# V0p2_Main_PCB2.net
KiCad netlist of a schematic drawn in EAGLE
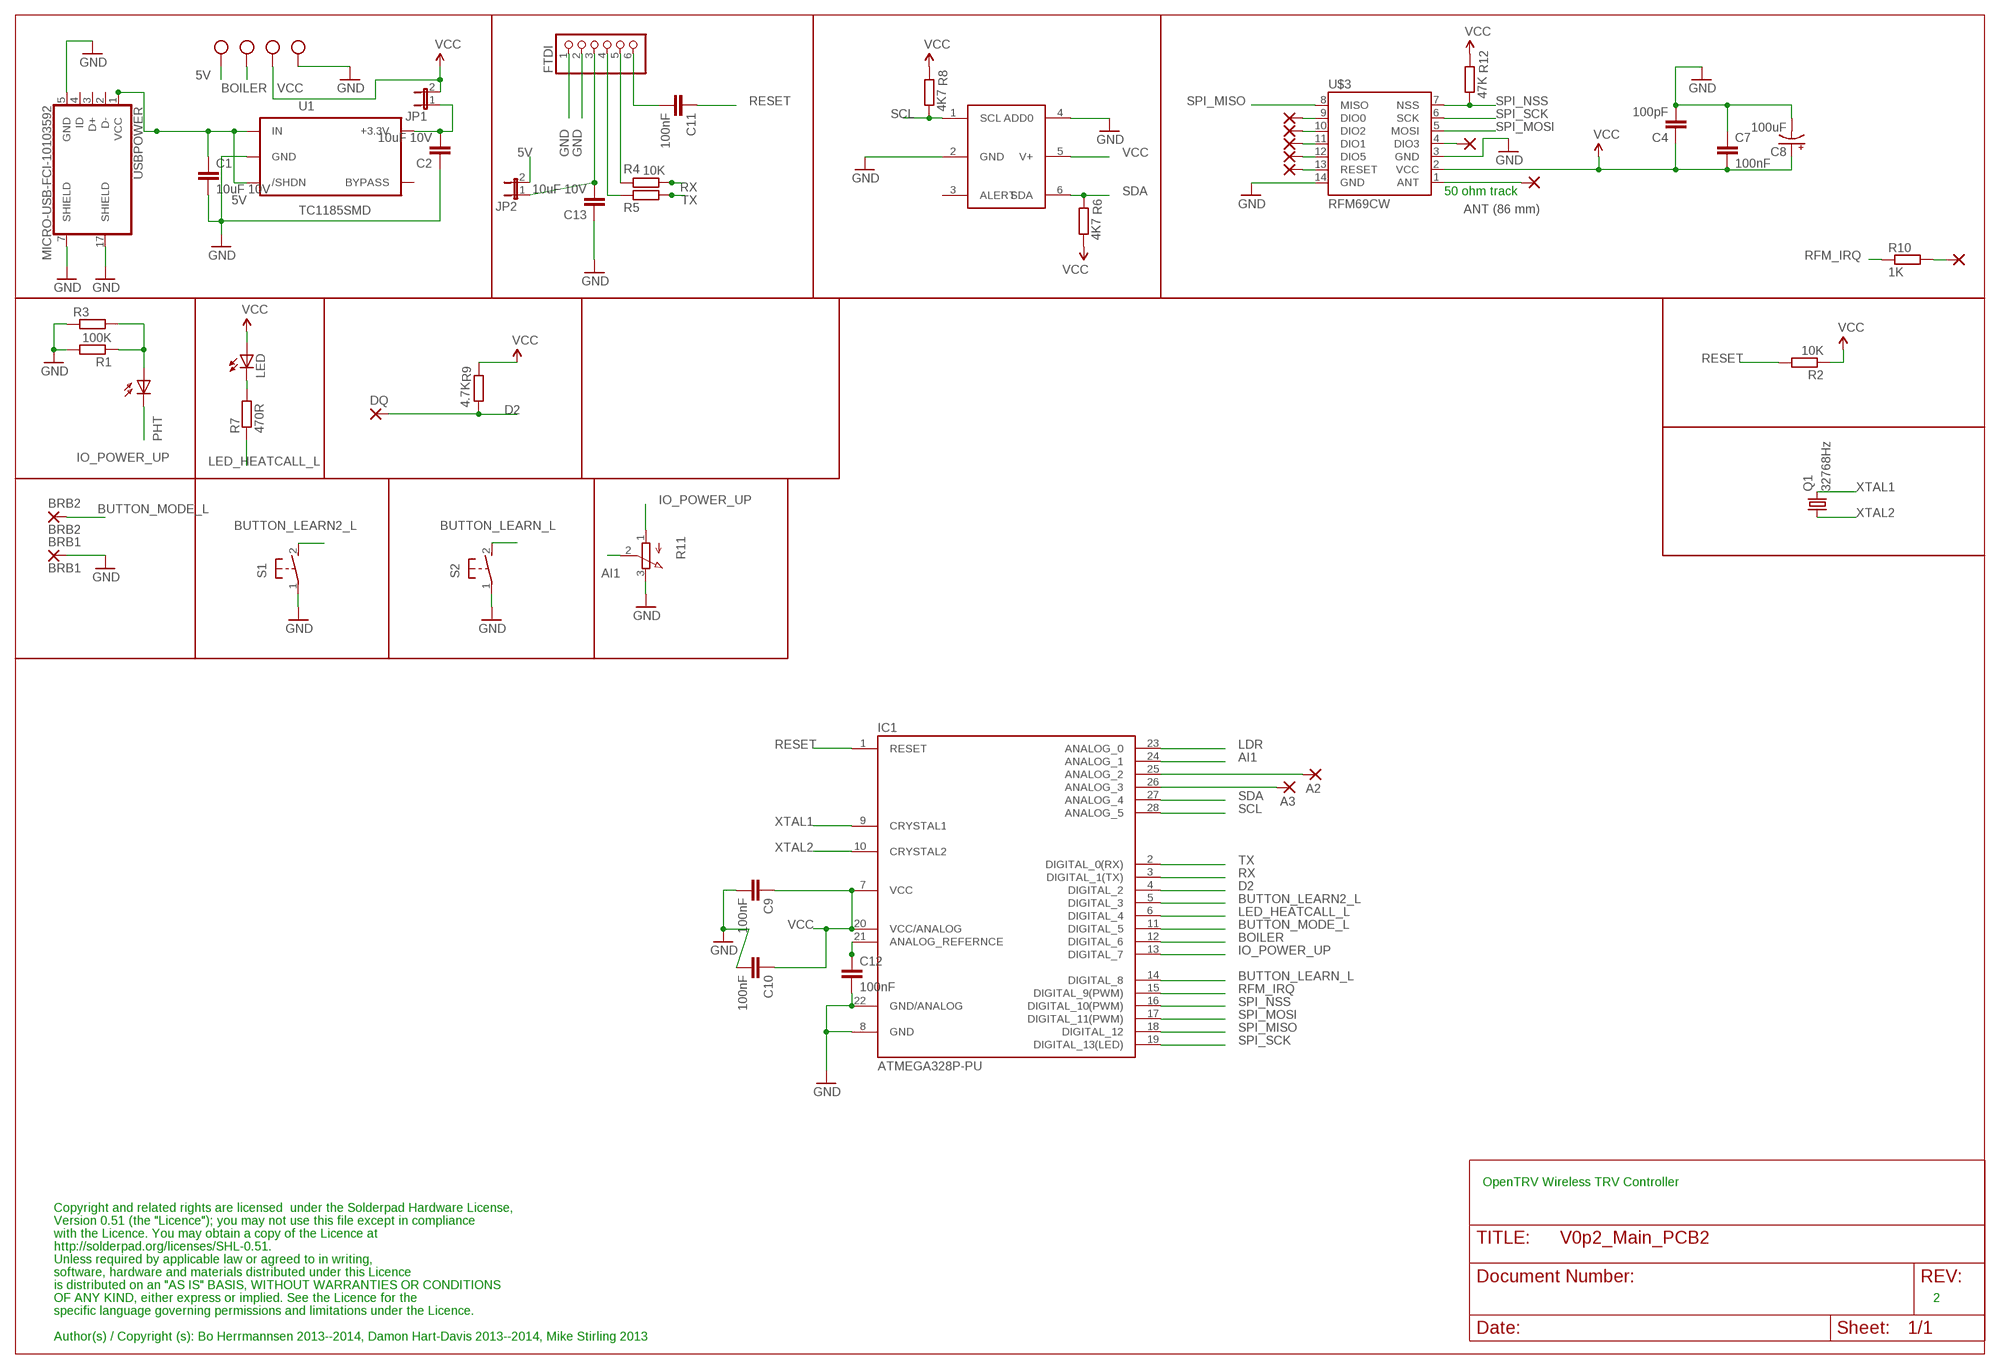
[diagram p0: schematic, sheet 1]

(export (version "E")
  (design (tool "Eeschema 10.0.6"))
  (components
    (comp (ref "A2")
      (value "2,15/1,0")
      (footprint "eagle-import:2,15_1,0")
      (libsource (lib "eagle-import") (part "2,15/1,0"))
    )
    (comp (ref "A3")
      (value "2,15/1,0")
      (footprint "eagle-import:2,15_1,0")
      (libsource (lib "eagle-import") (part "2,15/1,0"))
    )
    (comp (ref "ANT")
      (value "ANT (86 mm)")
      (footprint "eagle-import:2,15_1,0")
      (libsource (lib "eagle-import") (part "2,15/1,0"))
    )
    (comp (ref "BRB1")
      (value "BRB1")
      (footprint "eagle-import:2,15_1,0")
      (libsource (lib "eagle-import") (part "2,15/1,0"))
    )
    (comp (ref "BRB2")
      (value "BRB2")
      (footprint "eagle-import:2,15_1,0")
      (libsource (lib "eagle-import") (part "2,15/1,0"))
    )
    (comp (ref "C1")
      (value "10uF 10V")
      (footprint "eagle-import:C0603")
      (libsource (lib "eagle-import") (part "C-EUC0603"))
    )
    (comp (ref "C2")
      (value "10uF 10V")
      (footprint "eagle-import:C0603")
      (libsource (lib "eagle-import") (part "C-EUC0603"))
    )
    (comp (ref "C4")
      (value "100pF")
      (footprint "eagle-import:C0603")
      (libsource (lib "eagle-import") (part "C-EUC0603"))
    )
    (comp (ref "C7")
      (value "100nF")
      (footprint "eagle-import:C0603")
      (libsource (lib "eagle-import") (part "C-EUC0603"))
    )
    (comp (ref "C8")
      (value "100uF")
      (footprint "eagle-import:EIA3216")
      (libsource (lib "eagle-import") (part "CAP_POL1206"))
    )
    (comp (ref "C9")
      (value "100nF")
      (footprint "eagle-import:C0603")
      (libsource (lib "eagle-import") (part "C-EUC0603"))
    )
    (comp (ref "C10")
      (value "100nF")
      (footprint "eagle-import:C0603")
      (libsource (lib "eagle-import") (part "C-EUC0603"))
    )
    (comp (ref "C11")
      (value "100nF")
      (footprint "eagle-import:C0603")
      (libsource (lib "eagle-import") (part "C-EUC0603"))
    )
    (comp (ref "C12")
      (value "100nF")
      (footprint "eagle-import:C0603")
      (libsource (lib "eagle-import") (part "C-EUC0603"))
    )
    (comp (ref "C13")
      (value "10uF 10V")
      (footprint "eagle-import:C0603")
      (libsource (lib "eagle-import") (part "C-EUC0603"))
    )
    (comp (ref "DIO0")
      (value "ANT (86 mm)")
      (footprint "eagle-import:2,15_1,0")
      (libsource (lib "eagle-import") (part "2,15/1,0"))
    )
    (comp (ref "DIO1")
      (value "ANT (86 mm)")
      (footprint "eagle-import:2,15_1,0")
      (libsource (lib "eagle-import") (part "2,15/1,0"))
    )
    (comp (ref "DIO2")
      (value "ANT (86 mm)")
      (footprint "eagle-import:2,15_1,0")
      (libsource (lib "eagle-import") (part "2,15/1,0"))
    )
    (comp (ref "DIO3")
      (value "ANT (86 mm)")
      (footprint "eagle-import:2,15_1,0")
      (libsource (lib "eagle-import") (part "2,15/1,0"))
    )
    (comp (ref "DIO5")
      (value "ANT (86 mm)")
      (footprint "eagle-import:2,15_1,0")
      (libsource (lib "eagle-import") (part "2,15/1,0"))
    )
    (comp (ref "DQ")
      (value "2,15/1,0")
      (footprint "eagle-import:2,15_1,0")
      (libsource (lib "eagle-import") (part "2,15/1,0"))
    )
    (comp (ref "FTDI")
      (value "PINHD-1X6/90")
      (footprint "eagle-import:1X06_90")
      (libsource (lib "eagle-import") (part "PINHD-1X6/90"))
    )
    (comp (ref "IC1")
      (value "ATMEGA328P-PU")
      (footprint "eagle-import:DIL28-3")
      (libsource (lib "eagle-import") (part "ATMEGA8-PU"))
    )
    (comp (ref "IRQ")
      (value "ANT (86 mm)")
      (footprint "eagle-import:2,15_1,0")
      (libsource (lib "eagle-import") (part "2,15/1,0"))
    )
    (comp (ref "JP1")
      (value "JP1E")
      (footprint "eagle-import:JP1")
      (libsource (lib "eagle-import") (part "JP1E"))
    )
    (comp (ref "JP2")
      (value "JP1E")
      (footprint "eagle-import:JP1")
      (libsource (lib "eagle-import") (part "JP1E"))
    )
    (comp (ref "LED")
      (value "LED3MM")
      (footprint "eagle-import:LED3MM")
      (libsource (lib "eagle-import") (part "LED3MM"))
    )
    (comp (ref "PHT")
      (value "BPX65")
      (footprint "eagle-import:BPX65")
      (fields (field (name "MPN") "BPX65."))
      (libsource (lib "eagle-import") (part "BPX65"))
    )
    (comp (ref "Q1")
      (value "32768Hz")
      (footprint "eagle-import:MC-306")
      (fields (field (name "MPN") "MC-306 60.0KHZ  100PPM ,12.5PF"))
      (libsource (lib "eagle-import") (part "MC-306"))
    )
    (comp (ref "R1")
      (value "100K")
      (footprint "eagle-import:R0603")
      (libsource (lib "eagle-import") (part "R-EU_R0603"))
    )
    (comp (ref "R2")
      (value "10K")
      (footprint "eagle-import:R0603")
      (libsource (lib "eagle-import") (part "R-EU_R0603"))
    )
    (comp (ref "R3")
      (value "R-EU_0309/V")
      (footprint "eagle-import:0309V")
      (libsource (lib "eagle-import") (part "R-EU_0309/V"))
    )
    (comp (ref "R4")
      (value "10K")
      (footprint "eagle-import:R0603")
      (libsource (lib "eagle-import") (part "R-EU_R0603"))
    )
    (comp (ref "R5")
      (value "10K")
      (footprint "eagle-import:R0603")
      (libsource (lib "eagle-import") (part "R-EU_R0603"))
    )
    (comp (ref "R6")
      (value "4K7")
      (footprint "eagle-import:R0603")
      (libsource (lib "eagle-import") (part "R-EU_R0603"))
    )
    (comp (ref "R7")
      (value "470R")
      (footprint "eagle-import:R0603")
      (libsource (lib "eagle-import") (part "R-EU_R0603"))
    )
    (comp (ref "R8")
      (value "4K7")
      (footprint "eagle-import:R0603")
      (libsource (lib "eagle-import") (part "R-EU_R0603"))
    )
    (comp (ref "R9")
      (value "4.7K")
      (footprint "eagle-import:R0603")
      (libsource (lib "eagle-import") (part "R-EU_R0603"))
    )
    (comp (ref "R10")
      (value "1K")
      (footprint "eagle-import:R0603")
      (libsource (lib "eagle-import") (part "R-EU_R0603"))
    )
    (comp (ref "R11")
      (value "EVUE2A")
      (footprint "eagle-import:EVUE")
      (libsource (lib "eagle-import") (part "EVUE2A"))
    )
    (comp (ref "R12")
      (value "47K")
      (footprint "eagle-import:R0603")
      (libsource (lib "eagle-import") (part "R-EU_R0603"))
    )
    (comp (ref "RST")
      (value "ANT (86 mm)")
      (footprint "eagle-import:2,15_1,0")
      (libsource (lib "eagle-import") (part "2,15/1,0"))
    )
    (comp (ref "S1")
      (value "31-XX")
      (footprint "eagle-import:B3F-31XX")
      (libsource (lib "eagle-import") (part "31-XX"))
    )
    (comp (ref "S2")
      (value "31-XX")
      (footprint "eagle-import:B3F-31XX")
      (libsource (lib "eagle-import") (part "31-XX"))
    )
    (comp (ref "TMP1")
      (value "TMP1")
      (footprint "eagle-import:TMP112")
      (libsource (lib "eagle-import") (part "TMP112"))
    )
    (comp (ref "U$3")
      (value "RFM69CW")
      (footprint "eagle-import:RFM69")
      (libsource (lib "eagle-import") (part "RFM69SMD"))
    )
    (comp (ref "U1")
      (value "TC1185SMD")
      (footprint "eagle-import:TC1185")
      (libsource (lib "eagle-import") (part "TC1185SMD"))
    )
    (comp (ref "USBPOWER")
      (value "MICRO-USB-FCI-10103592")
      (footprint "eagle-import:MICRO-USB-FCI-10103592")
      (libsource (lib "eagle-import") (part "MICRO-USB-FCI-10103592"))
    )
    (comp (ref "X1")
      (value "W237-102")
      (footprint "eagle-import:SCREWTERMINAL")
      (fields (field (name "MPN") "237-102"))
      (libsource (lib "eagle-import") (part "W237-102"))
    )
    (comp (ref "X2")
      (value "W237-102")
      (footprint "eagle-import:SCREWTERMINAL")
      (fields (field (name "MPN") "237-102"))
      (libsource (lib "eagle-import") (part "W237-102"))
    )
  )
  (nets
    (net (code "1") (name "/5V") (class "Default")
      (node (ref "C1") (pin "1") (pinfunction "1_1") (pintype "passive"))
      (node (ref "JP2") (pin "2") (pinfunction "2_2") (pintype "passive"))
      (node (ref "U1") (pin "1") (pinfunction "IN_1") (pintype "passive"))
      (node (ref "U1") (pin "3") (pinfunction "/SHDN_3") (pintype "passive"))
      (node (ref "USBPOWER") (pin "1") (pinfunction "VCC_1") (pintype "bidirectional"))
      (node (ref "X1") (pin "2") (pinfunction "KL_2") (pintype "passive"))
    )
    (net (code "2") (name "/AI1") (class "Default")
      (node (ref "IC1") (pin "24") (pinfunction "ANALOG_1_24") (pintype "bidirectional"))
      (node (ref "R11") (pin "2") (pinfunction "S_2") (pintype "passive"))
    )
    (net (code "3") (name "/BOILER") (class "Default")
      (node (ref "IC1") (pin "12") (pinfunction "DIGITAL_6_12") (pintype "bidirectional"))
      (node (ref "X1") (pin "1") (pinfunction "KL_1") (pintype "passive"))
    )
    (net (code "4") (name "/BUTTON_LEARN2_L") (class "Default")
      (node (ref "IC1") (pin "5") (pinfunction "DIGITAL_3_5") (pintype "bidirectional"))
      (node (ref "S1") (pin "2") (pinfunction "S_2") (pintype "passive"))
    )
    (net (code "5") (name "/BUTTON_LEARN_L") (class "Default")
      (node (ref "IC1") (pin "14") (pinfunction "DIGITAL_8_14") (pintype "bidirectional"))
      (node (ref "S2") (pin "2") (pinfunction "S_2") (pintype "passive"))
    )
    (net (code "6") (name "/BUTTON_MODE_L") (class "Default")
      (node (ref "BRB2") (pin "1") (pinfunction "P_1") (pintype "passive"))
      (node (ref "IC1") (pin "11") (pinfunction "DIGITAL_5_11") (pintype "bidirectional"))
    )
    (net (code "7") (name "/D2") (class "Default")
      (node (ref "DQ") (pin "1") (pinfunction "P_1") (pintype "passive"))
      (node (ref "IC1") (pin "4") (pinfunction "DIGITAL_2_4") (pintype "bidirectional"))
      (node (ref "R9") (pin "1") (pinfunction "1_1") (pintype "passive"))
    )
    (net (code "8") (name "/IO_POWER_UP") (class "Default")
      (node (ref "IC1") (pin "13") (pinfunction "DIGITAL_7_13") (pintype "bidirectional"))
      (node (ref "PHT") (pin "K") (pinfunction "C_K") (pintype "passive"))
      (node (ref "R11") (pin "1") (pinfunction "A_1") (pintype "passive"))
    )
    (net (code "9") (name "/LDR") (class "Default")
      (node (ref "IC1") (pin "23") (pinfunction "ANALOG_0_23") (pintype "bidirectional"))
      (node (ref "PHT") (pin "A") (pinfunction "A_A") (pintype "passive"))
      (node (ref "R1") (pin "1") (pinfunction "1_1") (pintype "passive"))
      (node (ref "R3") (pin "2") (pinfunction "2_2") (pintype "passive"))
    )
    (net (code "10") (name "/LED_HEATCALL_L") (class "Default")
      (node (ref "IC1") (pin "6") (pinfunction "DIGITAL_4_6") (pintype "bidirectional"))
      (node (ref "R7") (pin "1") (pinfunction "1_1") (pintype "passive"))
    )
    (net (code "11") (name "/RESET") (class "Default")
      (node (ref "C11") (pin "1") (pinfunction "1_1") (pintype "passive"))
      (node (ref "IC1") (pin "1") (pinfunction "RESET_1") (pintype "bidirectional"))
      (node (ref "R2") (pin "2") (pinfunction "2_2") (pintype "passive"))
    )
    (net (code "12") (name "/RFM_IRQ") (class "Default")
      (node (ref "IC1") (pin "15") (pinfunction "DIGITAL_9(PWM)_15") (pintype "bidirectional"))
      (node (ref "R10") (pin "1") (pinfunction "1_1") (pintype "passive"))
    )
    (net (code "13") (name "/RX") (class "Default")
      (node (ref "IC1") (pin "3") (pinfunction "DIGITAL_1(TX)_3") (pintype "bidirectional"))
      (node (ref "R4") (pin "1") (pinfunction "1_1") (pintype "passive"))
    )
    (net (code "14") (name "/SCL") (class "Default")
      (node (ref "IC1") (pin "28") (pinfunction "ANALOG_5_28") (pintype "bidirectional"))
      (node (ref "R8") (pin "1") (pinfunction "1_1") (pintype "passive"))
      (node (ref "TMP1") (pin "1") (pinfunction "SCL_1") (pintype "bidirectional"))
    )
    (net (code "15") (name "/SDA") (class "Default")
      (node (ref "IC1") (pin "27") (pinfunction "ANALOG_4_27") (pintype "bidirectional"))
      (node (ref "R6") (pin "2") (pinfunction "2_2") (pintype "passive"))
      (node (ref "TMP1") (pin "6") (pinfunction "SDA_6") (pintype "bidirectional"))
    )
    (net (code "16") (name "/SPI_MISO") (class "Default")
      (node (ref "IC1") (pin "18") (pinfunction "DIGITAL_12_18") (pintype "bidirectional"))
      (node (ref "U$3") (pin "8") (pinfunction "MISO_8") (pintype "input"))
    )
    (net (code "17") (name "/SPI_MOSI") (class "Default")
      (node (ref "IC1") (pin "17") (pinfunction "DIGITAL_11(PWM)_17") (pintype "bidirectional"))
      (node (ref "U$3") (pin "5") (pinfunction "MOSI_5") (pintype "input"))
    )
    (net (code "18") (name "/SPI_NSS") (class "Default")
      (node (ref "IC1") (pin "16") (pinfunction "DIGITAL_10(PWM)_16") (pintype "bidirectional"))
      (node (ref "R12") (pin "1") (pinfunction "1_1") (pintype "passive"))
      (node (ref "U$3") (pin "7") (pinfunction "NSS_7") (pintype "output"))
    )
    (net (code "19") (name "/SPI_SCK") (class "Default")
      (node (ref "IC1") (pin "19") (pinfunction "DIGITAL_13(LED)_19") (pintype "bidirectional"))
      (node (ref "U$3") (pin "6") (pinfunction "SCK_6") (pintype "input"))
    )
    (net (code "20") (name "/TX") (class "Default")
      (node (ref "IC1") (pin "2") (pinfunction "DIGITAL_0(RX)_2") (pintype "bidirectional"))
      (node (ref "R5") (pin "1") (pinfunction "1_1") (pintype "passive"))
    )
    (net (code "21") (name "/XTAL1") (class "Default")
      (node (ref "IC1") (pin "9") (pinfunction "CRYSTAL1_9") (pintype "bidirectional"))
      (node (ref "Q1") (pin "4") (pinfunction "2_4") (pintype "passive"))
    )
    (net (code "22") (name "/XTAL2") (class "Default")
      (node (ref "IC1") (pin "10") (pinfunction "CRYSTAL2_10") (pintype "bidirectional"))
      (node (ref "Q1") (pin "1") (pinfunction "1_1") (pintype "passive"))
    )
    (net (code "23") (name "GND") (class "Default")
      (node (ref "BRB1") (pin "1") (pinfunction "P_1") (pintype "passive"))
      (node (ref "C1") (pin "2") (pinfunction "2_2") (pintype "passive"))
      (node (ref "C10") (pin "2") (pinfunction "2_2") (pintype "passive"))
      (node (ref "C12") (pin "2") (pinfunction "2_2") (pintype "passive"))
      (node (ref "C13") (pin "1") (pinfunction "1_1") (pintype "passive"))
      (node (ref "C2") (pin "1") (pinfunction "1_1") (pintype "passive"))
      (node (ref "C4") (pin "2") (pinfunction "2_2") (pintype "passive"))
      (node (ref "C7") (pin "1") (pinfunction "1_1") (pintype "passive"))
      (node (ref "C8") (pin "C") (pinfunction "-_C") (pintype "passive"))
      (node (ref "C9") (pin "2") (pinfunction "2_2") (pintype "passive"))
      (node (ref "FTDI") (pin "1") (pinfunction "1_1") (pintype "passive"))
      (node (ref "FTDI") (pin "2") (pinfunction "2_2") (pintype "passive"))
      (node (ref "IC1") (pin "22") (pinfunction "GND/ANALOG_22") (pintype "power_in"))
      (node (ref "IC1") (pin "8") (pinfunction "GND_8") (pintype "power_in"))
      (node (ref "R1") (pin "2") (pinfunction "2_2") (pintype "passive"))
      (node (ref "R11") (pin "3") (pinfunction "E_3") (pintype "passive"))
      (node (ref "R3") (pin "1") (pinfunction "1_1") (pintype "passive"))
      (node (ref "S1") (pin "1") (pinfunction "P_1") (pintype "passive"))
      (node (ref "S2") (pin "1") (pinfunction "P_1") (pintype "passive"))
      (node (ref "TMP1") (pin "2") (pinfunction "GND_2") (pintype "bidirectional"))
      (node (ref "TMP1") (pin "4") (pinfunction "ADD0_4") (pintype "bidirectional"))
      (node (ref "U$3") (pin "14") (pinfunction "GND_14") (pintype "power_in"))
      (node (ref "U$3") (pin "3") (pinfunction "GND_3") (pintype "power_in"))
      (node (ref "U1") (pin "2") (pinfunction "GND_2") (pintype "passive"))
      (node (ref "USBPOWER") (pin "17") (pinfunction "SHIELD_17") (pintype "bidirectional"))
      (node (ref "USBPOWER") (pin "5") (pinfunction "GND_5") (pintype "bidirectional"))
      (node (ref "USBPOWER") (pin "7") (pinfunction "SHIELD_7") (pintype "bidirectional"))
      (node (ref "X2") (pin "2") (pinfunction "KL_2") (pintype "passive"))
    )
    (net (code "24") (name "Net-(A2-P)") (class "Default")
      (node (ref "A2") (pin "1") (pinfunction "P_1") (pintype "passive"))
      (node (ref "IC1") (pin "25") (pinfunction "ANALOG_2_25") (pintype "bidirectional"))
    )
    (net (code "25") (name "Net-(A3-P)") (class "Default")
      (node (ref "A3") (pin "1") (pinfunction "P_1") (pintype "passive"))
      (node (ref "IC1") (pin "26") (pinfunction "ANALOG_3_26") (pintype "bidirectional"))
    )
    (net (code "26") (name "Net-(ANT-P)") (class "Default")
      (node (ref "ANT") (pin "1") (pinfunction "P_1") (pintype "passive"))
      (node (ref "U$3") (pin "1") (pinfunction "ANT_1") (pintype "bidirectional"))
    )
    (net (code "27") (name "Net-(C11-Pad2)") (class "Default")
      (node (ref "C11") (pin "2") (pinfunction "2_2") (pintype "passive"))
      (node (ref "FTDI") (pin "6") (pinfunction "6_6") (pintype "passive"))
    )
    (net (code "28") (name "Net-(C13-Pad2)") (class "Default")
      (node (ref "C13") (pin "2") (pinfunction "2_2") (pintype "passive"))
      (node (ref "FTDI") (pin "3") (pinfunction "3_3") (pintype "passive"))
      (node (ref "JP2") (pin "1") (pinfunction "1_1") (pintype "passive"))
    )
    (net (code "29") (name "Net-(DIO0-P)") (class "Default")
      (node (ref "DIO0") (pin "1") (pinfunction "P_1") (pintype "passive"))
      (node (ref "U$3") (pin "9") (pinfunction "DIO0_9") (pintype "output"))
    )
    (net (code "30") (name "Net-(DIO1-P)") (class "Default")
      (node (ref "DIO1") (pin "1") (pinfunction "P_1") (pintype "passive"))
      (node (ref "U$3") (pin "11") (pinfunction "DIO1_11") (pintype "input"))
    )
    (net (code "31") (name "Net-(DIO2-P)") (class "Default")
      (node (ref "DIO2") (pin "1") (pinfunction "P_1") (pintype "passive"))
      (node (ref "U$3") (pin "10") (pinfunction "DIO2_10") (pintype "input"))
    )
    (net (code "32") (name "Net-(DIO3-P)") (class "Default")
      (node (ref "DIO3") (pin "1") (pinfunction "P_1") (pintype "passive"))
      (node (ref "U$3") (pin "4") (pinfunction "DIO3_4") (pintype "input"))
    )
    (net (code "33") (name "Net-(DIO5-P)") (class "Default")
      (node (ref "DIO5") (pin "1") (pinfunction "P_1") (pintype "passive"))
      (node (ref "U$3") (pin "12") (pinfunction "DIO5_12") (pintype "input"))
    )
    (net (code "34") (name "Net-(FTDI-Pad4)") (class "Default")
      (node (ref "FTDI") (pin "4") (pinfunction "4_4") (pintype "passive"))
      (node (ref "R5") (pin "2") (pinfunction "2_2") (pintype "passive"))
    )
    (net (code "35") (name "Net-(FTDI-Pad5)") (class "Default")
      (node (ref "FTDI") (pin "5") (pinfunction "5_5") (pintype "passive"))
      (node (ref "R4") (pin "2") (pinfunction "2_2") (pintype "passive"))
    )
    (net (code "36") (name "Net-(IC1-ANALOG_REFERNCE)") (class "Default")
      (node (ref "C12") (pin "1") (pinfunction "1_1") (pintype "passive"))
      (node (ref "IC1") (pin "21") (pinfunction "ANALOG_REFERNCE_21") (pintype "passive"))
    )
    (net (code "37") (name "Net-(IRQ-P)") (class "Default")
      (node (ref "IRQ") (pin "1") (pinfunction "P_1") (pintype "passive"))
      (node (ref "R10") (pin "2") (pinfunction "2_2") (pintype "passive"))
    )
    (net (code "38") (name "Net-(LED-C)") (class "Default")
      (node (ref "LED") (pin "K") (pinfunction "C_K") (pintype "passive"))
      (node (ref "R7") (pin "2") (pinfunction "2_2") (pintype "passive"))
    )
    (net (code "39") (name "Net-(RST-P)") (class "Default")
      (node (ref "RST") (pin "1") (pinfunction "P_1") (pintype "passive"))
      (node (ref "U$3") (pin "13") (pinfunction "RESET_13") (pintype "power_in"))
    )
    (net (code "40") (name "Net-(U1-+3.3V)") (class "Default")
      (node (ref "C2") (pin "2") (pinfunction "2_2") (pintype "passive"))
      (node (ref "JP1") (pin "1") (pinfunction "1_1") (pintype "passive"))
      (node (ref "U1") (pin "5") (pinfunction "+3.3V_5") (pintype "power_in"))
    )
    (net (code "41") (name "VCC") (class "Default")
      (node (ref "C10") (pin "1") (pinfunction "1_1") (pintype "passive"))
      (node (ref "C4") (pin "1") (pinfunction "1_1") (pintype "passive"))
      (node (ref "C7") (pin "2") (pinfunction "2_2") (pintype "passive"))
      (node (ref "C8") (pin "A") (pinfunction "+_A") (pintype "passive"))
      (node (ref "C9") (pin "1") (pinfunction "1_1") (pintype "passive"))
      (node (ref "IC1") (pin "20") (pinfunction "VCC/ANALOG_20") (pintype "passive"))
      (node (ref "IC1") (pin "7") (pinfunction "VCC_7") (pintype "power_in"))
      (node (ref "JP1") (pin "2") (pinfunction "2_2") (pintype "passive"))
      (node (ref "LED") (pin "A") (pinfunction "A_A") (pintype "passive"))
      (node (ref "R12") (pin "2") (pinfunction "2_2") (pintype "passive"))
      (node (ref "R2") (pin "1") (pinfunction "1_1") (pintype "passive"))
      (node (ref "R6") (pin "1") (pinfunction "1_1") (pintype "passive"))
      (node (ref "R8") (pin "2") (pinfunction "2_2") (pintype "passive"))
      (node (ref "R9") (pin "2") (pinfunction "2_2") (pintype "passive"))
      (node (ref "TMP1") (pin "5") (pinfunction "V+_5") (pintype "bidirectional"))
      (node (ref "U$3") (pin "2") (pinfunction "VCC_2") (pintype "bidirectional"))
      (node (ref "X2") (pin "1") (pinfunction "KL_1") (pintype "passive"))
    )
    (net (code "42") (name "unconnected-(TMP1-ALERT-Pad3)") (class "Default")
      (node (ref "TMP1") (pin "3") (pinfunction "ALERT_3") (pintype "bidirectional"))
    )
    (net (code "43") (name "unconnected-(U1-BYPASS-Pad4)") (class "Default")
      (node (ref "U1") (pin "4") (pinfunction "BYPASS_4") (pintype "passive"))
    )
    (net (code "44") (name "unconnected-(USBPOWER-D+-Pad3)") (class "Default")
      (node (ref "USBPOWER") (pin "3") (pinfunction "D+_3") (pintype "bidirectional"))
    )
    (net (code "45") (name "unconnected-(USBPOWER-D--Pad2)") (class "Default")
      (node (ref "USBPOWER") (pin "2") (pinfunction "D-_2") (pintype "bidirectional"))
    )
    (net (code "46") (name "unconnected-(USBPOWER-ID-Pad4)") (class "Default")
      (node (ref "USBPOWER") (pin "4") (pinfunction "ID_4") (pintype "bidirectional"))
    )
  )
)
